# BQ40Z50.net
KiCad netlist of a schematic drawn in Altium Designer
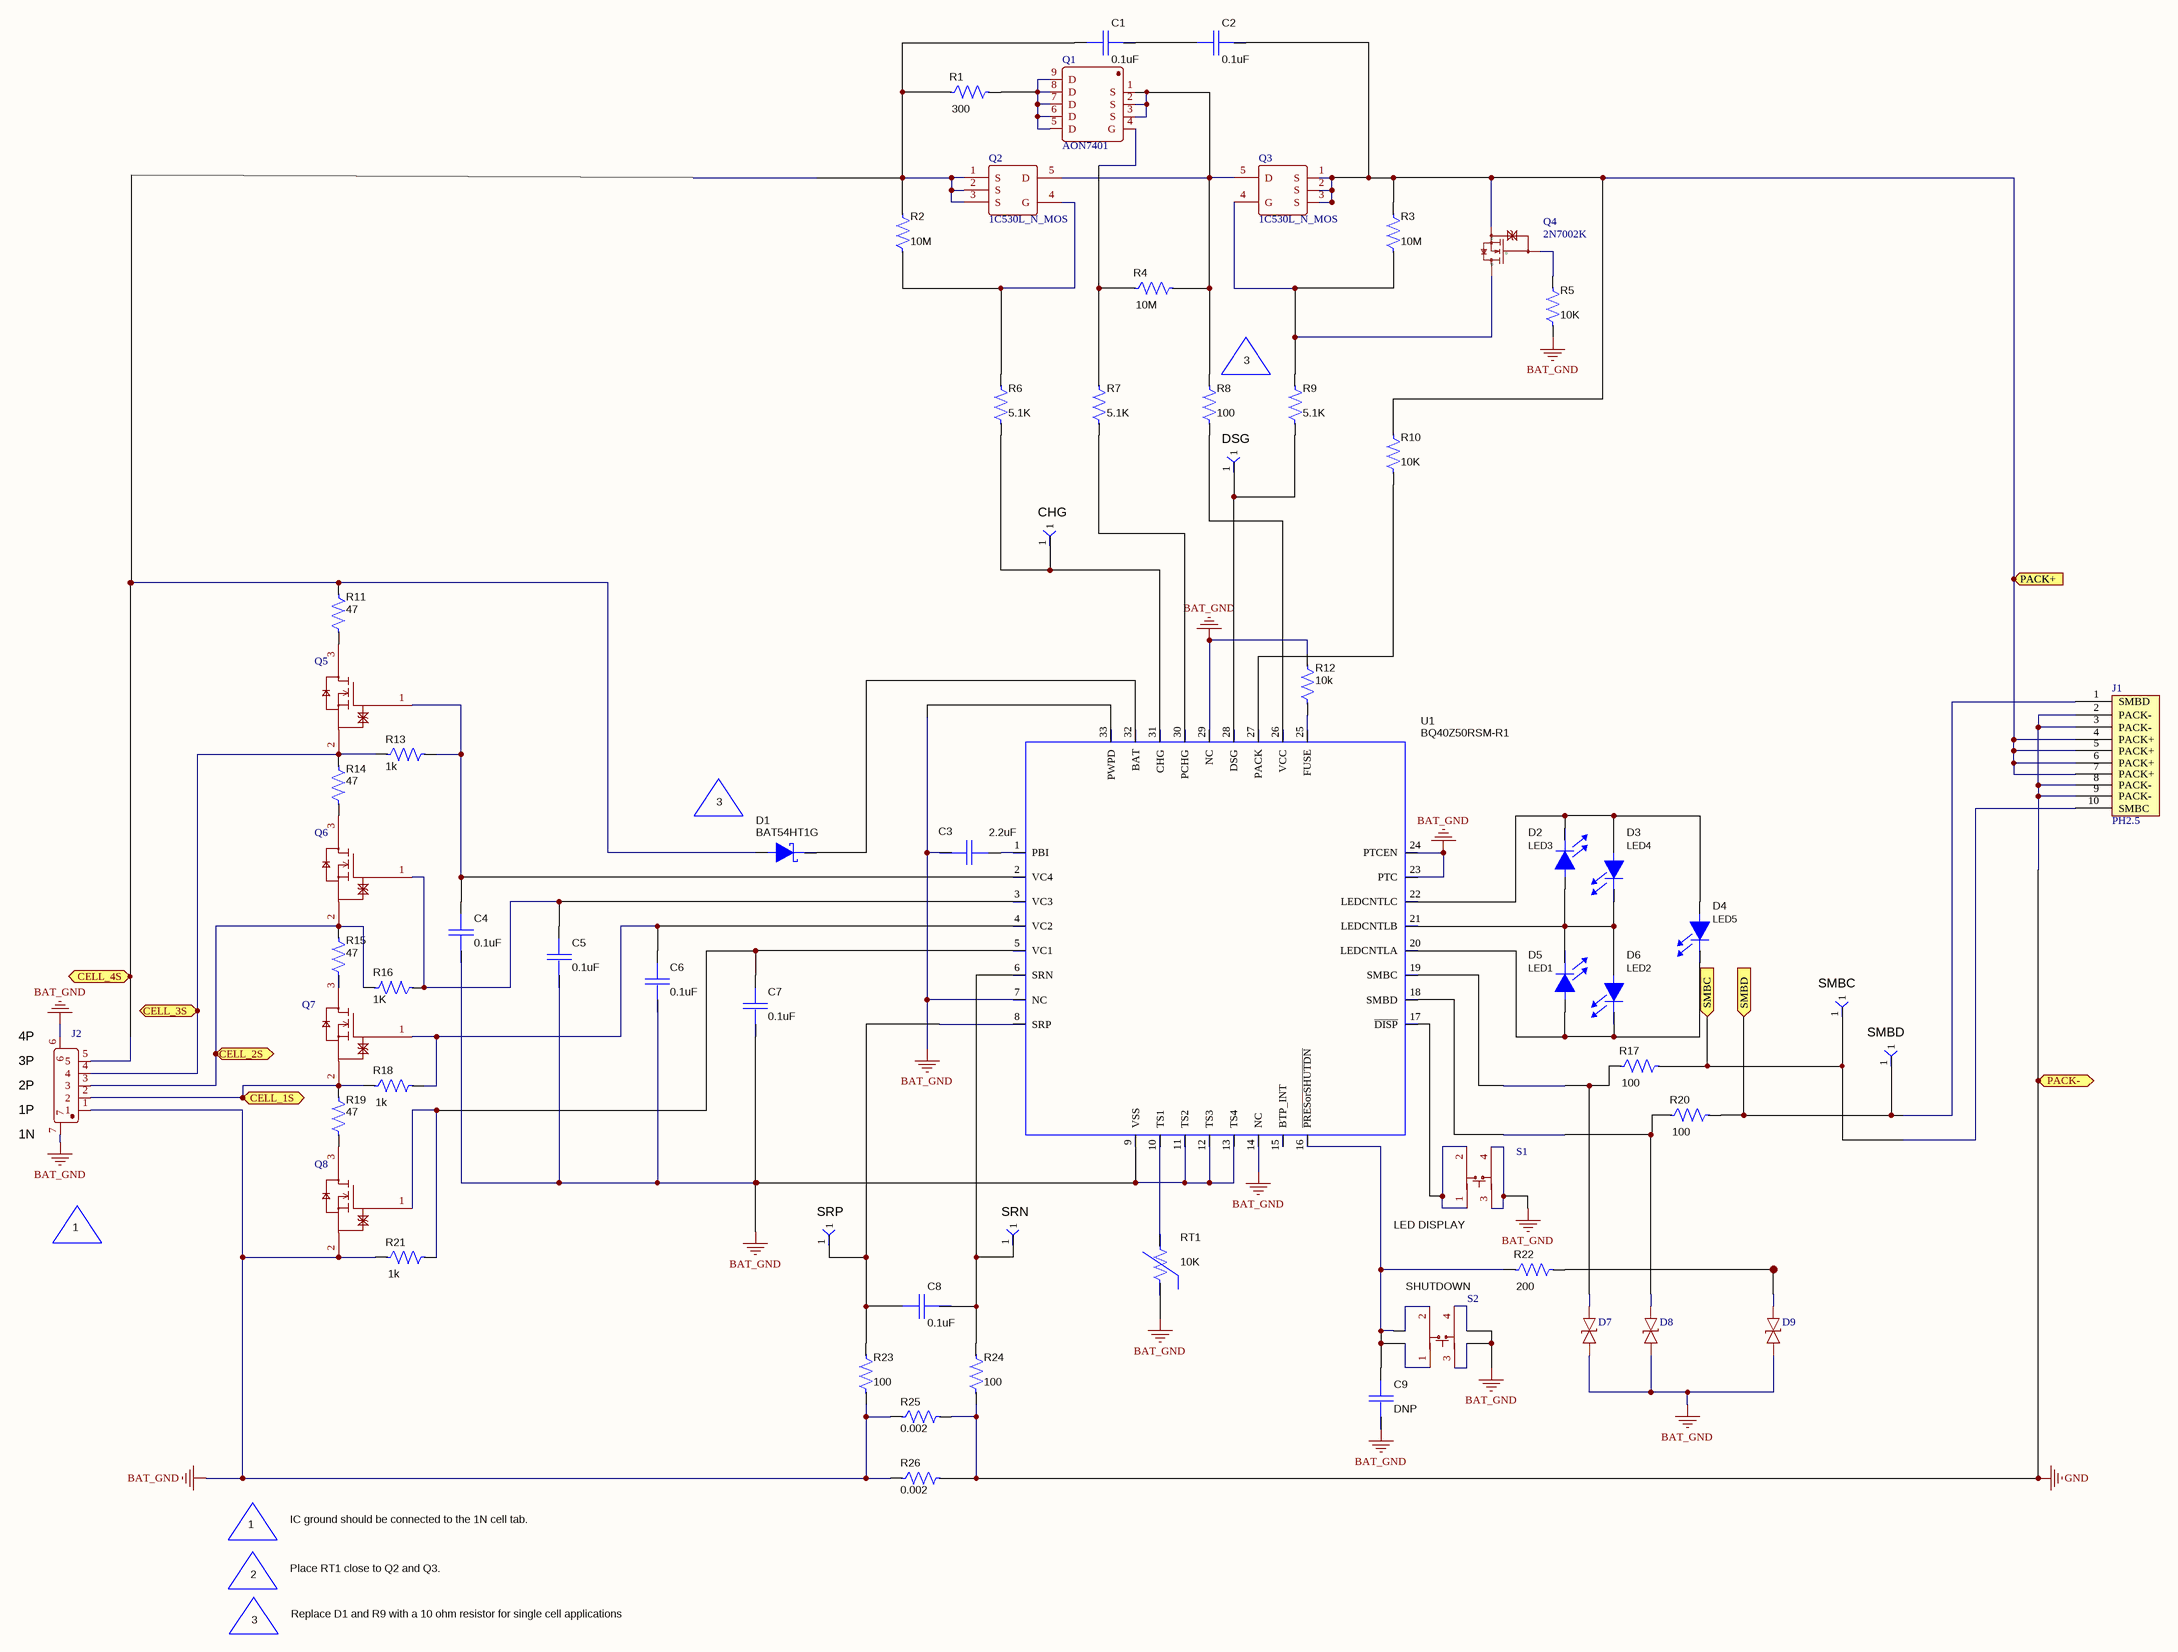
[diagram p0: BQ40Z50.SchDoc]

(export (version "E")
  (design (tool "Eeschema 10.0.6"))
  (components
    (comp (ref "C1")
      (value "0.1uF")
      (footprint "C603")
      (description "Capacitor, Ceramic Chip, 50V, X7R, ±20%")
      (fields (field (name "MANUFACTURER") "Kemet") (field (name "PARTNUMBER") "C0603C104M5RACTU"))
      (libsource (lib "PADSlegacy_Passive") (part "C0603"))
    )
    (comp (ref "C2")
      (value "0.1uF")
      (footprint "C603")
      (description "Capacitor, Ceramic Chip, 50V, X7R, ±20%")
      (fields (field (name "MANUFACTURER") "Kemet") (field (name "PARTNUMBER") "C0603C104M5RACTU"))
      (libsource (lib "PADSlegacy_Passive") (part "C0603"))
    )
    (comp (ref "C3")
      (value "2.2uF")
      (footprint "C0805")
      (description "Capacitor, Ceramic Chip, 25V, X7R ±20%")
      (fields (field (name "MANUFACTURER") "TDK") (field (name "PARTNUMBER") "C2012X7R1E225M085AB"))
      (libsource (lib "PADSlegacy_Passive") (part "C0805"))
    )
    (comp (ref "C4")
      (value "0.1uF")
      (footprint "C603")
      (description "Capacitor, Ceramic Chip, 50V, X7R, ±20%")
      (fields (field (name "MANUFACTURER") "Kemet") (field (name "PARTNUMBER") "C0603C104M5RACTU"))
      (libsource (lib "PADSlegacy_Passive") (part "C0603"))
    )
    (comp (ref "C5")
      (value "0.1uF")
      (footprint "C603")
      (description "Capacitor, Ceramic Chip, 50V, X7R, ±20%")
      (fields (field (name "MANUFACTURER") "Kemet") (field (name "PARTNUMBER") "C0603C104M5RACTU"))
      (libsource (lib "PADSlegacy_Passive") (part "C0603"))
    )
    (comp (ref "C6")
      (value "0.1uF")
      (footprint "C603")
      (description "Capacitor, Ceramic Chip, 50V, X7R, ±20%")
      (fields (field (name "MANUFACTURER") "Kemet") (field (name "PARTNUMBER") "C0603C104M5RACTU"))
      (libsource (lib "PADSlegacy_Passive") (part "C0603"))
    )
    (comp (ref "C7")
      (value "0.1uF")
      (footprint "C603")
      (description "Capacitor, Ceramic Chip, 50V, X7R, ±20%")
      (fields (field (name "MANUFACTURER") "Kemet") (field (name "PARTNUMBER") "C0603C104M5RACTU"))
      (libsource (lib "PADSlegacy_Passive") (part "C0603"))
    )
    (comp (ref "C8")
      (value "0.1uF")
      (footprint "C603")
      (description "Capacitor, Ceramic Chip, 50V, X7R, ±20%")
      (fields (field (name "MANUFACTURER") "Kemet") (field (name "PARTNUMBER") "C0603C104M5RACTU"))
      (libsource (lib "PADSlegacy_Passive") (part "C0603"))
    )
    (comp (ref "C9")
      (value "DNP")
      (footprint "C603")
      (description "Capacitor, Ceramic Chip, 50V, X7R, ±20%")
      (fields (field (name "MANUFACTURER") "Kemet") (field (name "PARTNUMBER") "C0603C104M5RACTU"))
      (libsource (lib "PADSlegacy_Passive") (part "C0603"))
    )
    (comp (ref "D1")
      (value "BAT54HT1G")
      (footprint "SOD-323")
      (description "Diode, Schottky, 200-mA, 30-V")
      (fields (field (name "MANUFACTURER") "On Semi") (field (name "Comment") "D-BAT54HT1"))
      (libsource (lib "PADSlegacy_Active") (part "D-BAT54HT1"))
    )
    (comp (ref "D2")
      (value "D_LED_SML-LXR1206USBC-TR")
      (footprint "LED0805")
      (description "Diode, LED, 2X3mm 565nm GRN WTR CLR SMD")
      (fields (field (name "PARTNUMBER") "SML-LX23GC") (field (name "MANUFACTURER") "Lumex"))
      (libsource (lib "PADSlegacy_Active") (part "D_LED_SML-LXR1206USBC-TR"))
    )
    (comp (ref "D3")
      (value "D_LED_SML-LXR1206USBC-TR")
      (footprint "LED0805")
      (description "Diode, LED, 2X3mm 565nm GRN WTR CLR SMD")
      (fields (field (name "PARTNUMBER") "SML-LX23GC") (field (name "MANUFACTURER") "Lumex"))
      (libsource (lib "PADSlegacy_Active") (part "D_LED_SML-LXR1206USBC-TR"))
    )
    (comp (ref "D4")
      (value "D_LED_SML-LXR1206USBC-TR")
      (footprint "LED0805")
      (description "Diode, LED, 2X3mm 565nm GRN WTR CLR SMD")
      (fields (field (name "PARTNUMBER") "SML-LX23GC") (field (name "MANUFACTURER") "Lumex"))
      (libsource (lib "PADSlegacy_Active") (part "D_LED_SML-LXR1206USBC-TR"))
    )
    (comp (ref "D5")
      (value "D_LED_SML-LXR1206USBC-TR")
      (footprint "LED0805")
      (description "Diode, LED, 2X3mm 565nm GRN WTR CLR SMD")
      (fields (field (name "PARTNUMBER") "SML-LX23GC") (field (name "MANUFACTURER") "Lumex"))
      (libsource (lib "PADSlegacy_Active") (part "D_LED_SML-LXR1206USBC-TR"))
    )
    (comp (ref "D6")
      (value "D_LED_SML-LXR1206USBC-TR")
      (footprint "LED0805")
      (description "Diode, LED, 2X3mm 565nm GRN WTR CLR SMD")
      (fields (field (name "PARTNUMBER") "SML-LX23GC") (field (name "MANUFACTURER") "Lumex"))
      (libsource (lib "PADSlegacy_Active") (part "D_LED_SML-LXR1206USBC-TR"))
    )
    (comp (ref "D7")
      (value "ESD_Diode")
      (footprint "ESD_Diode")
      (libsource (lib "BQ4050") (part "ESD_Diode"))
    )
    (comp (ref "D8")
      (value "ESD_Diode")
      (footprint "ESD_Diode")
      (libsource (lib "BQ4050") (part "ESD_Diode"))
    )
    (comp (ref "D9")
      (value "ESD_Diode")
      (footprint "ESD_Diode")
      (libsource (lib "BQ4050") (part "ESD_Diode"))
    )
    (comp (ref "J1") (value "PH2.5") (footprint "PH2.5") (libsource (lib "BQ4050") (part "PH2.5")))
    (comp (ref "J2") (value "SMD_1.25") (footprint "SMD_1.25") (libsource (lib "BQ4050") (part "SMD_1.25")))
    (comp (ref "Q1") (value "AON7401") (footprint "DFN-8") (libsource (lib "BQ4050") (part "AON7401")))
    (comp (ref "Q2")
      (value "1C530L_N_MOS")
      (footprint "LFPAK")
      (libsource (lib "BQ4050") (part "1C530L_N_MOS"))
    )
    (comp (ref "Q3")
      (value "1C530L_N_MOS")
      (footprint "LFPAK")
      (libsource (lib "BQ4050") (part "1C530L_N_MOS"))
    )
    (comp (ref "Q4") (value "2N7002K") (footprint "2N7002K") (libsource (lib "BQ4050") (part "2N7002K")))
    (comp (ref "Q5")
      (value "DMN601K")
      (footprint "SOT-23 - duplicate")
      (libsource (lib "BQ4050") (part "DMN601K"))
    )
    (comp (ref "Q6")
      (value "DMN601K")
      (footprint "SOT-23 - duplicate")
      (libsource (lib "BQ4050") (part "DMN601K"))
    )
    (comp (ref "Q7")
      (value "DMN601K")
      (footprint "SOT-23 - duplicate")
      (libsource (lib "BQ4050") (part "DMN601K"))
    )
    (comp (ref "Q8")
      (value "DMN601K")
      (footprint "SOT-23 - duplicate")
      (libsource (lib "BQ4050") (part "DMN601K"))
    )
    (comp (ref "R1")
      (value "300")
      (footprint "R2512")
      (description "Resistor, Chip 1W, 5%")
      (fields (field (name "PARTNUMBER") "CRCW2512300RJNEG") (field (name "MANUFACTURER") "Vishay-Dale"))
      (libsource (lib "PADSlegacy_Passive") (part "R2512_5%"))
    )
    (comp (ref "R2")
      (value "10M")
      (footprint "0603")
      (description "Resistor, Chip, 1/10W, 5%")
      (fields (field (name "PARTNUMBER") "CRCW060310M0JNEA") (field (name "MANUFACTURER") "Vishay-Dale"))
      (libsource (lib "PADSlegacy_Passive") (part "R0603_1%"))
    )
    (comp (ref "R3")
      (value "10M")
      (footprint "0603")
      (description "Resistor, Chip, 1/10W, 5%")
      (fields (field (name "PARTNUMBER") "CRCW060310M0JNEA") (field (name "MANUFACTURER") "Vishay-Dale"))
      (libsource (lib "PADSlegacy_Passive") (part "R0603_1%"))
    )
    (comp (ref "R4")
      (value "10M")
      (footprint "0603")
      (description "Resistor, Chip, 1/10W, 5%")
      (fields (field (name "PARTNUMBER") "CRCW060310M0JNEA") (field (name "MANUFACTURER") "Vishay-Dale"))
      (libsource (lib "PADSlegacy_Passive") (part "R0603_1%"))
    )
    (comp (ref "R5")
      (value "10K")
      (footprint "0603")
      (description "Resistor, Chip, 1/10W, 5%")
      (fields (field (name "PARTNUMBER") "CRCW060310M0JNEA") (field (name "MANUFACTURER") "Vishay-Dale"))
      (libsource (lib "PADSlegacy_Passive") (part "R0603_1%"))
    )
    (comp (ref "R6")
      (value "5.1K")
      (footprint "0603")
      (description "Resistor, Chip, 1/10W, 5%")
      (fields (field (name "PARTNUMBER") "CRCW06035K10JNEA") (field (name "MANUFACTURER") "Vishay-Dale"))
      (libsource (lib "PADSlegacy_Passive") (part "R0603_1%"))
    )
    (comp (ref "R7")
      (value "5.1K")
      (footprint "0603")
      (description "Resistor, Chip, 1/10W, 5%")
      (fields (field (name "PARTNUMBER") "CRCW06035K10JNEA") (field (name "MANUFACTURER") "Vishay-Dale"))
      (libsource (lib "PADSlegacy_Passive") (part "R0603_1%"))
    )
    (comp (ref "R8")
      (value "100")
      (footprint "0603")
      (description "Resistor, Chip, 1/10W, 5%")
      (fields (field (name "PARTNUMBER") "CRCW0603100RJNEAHP") (field (name "MANUFACTURER") "Vishay-Dale"))
      (libsource (lib "PADSlegacy_Passive") (part "R0603_1%"))
    )
    (comp (ref "R9")
      (value "5.1K")
      (footprint "0603")
      (description "Resistor, Chip, 1/10W, 5%")
      (fields (field (name "PARTNUMBER") "CRCW06035K10JNEA") (field (name "MANUFACTURER") "Vishay-Dale"))
      (libsource (lib "PADSlegacy_Passive") (part "R0603_1%"))
    )
    (comp (ref "R10")
      (value "10K")
      (footprint "0603")
      (description "Resistor, Chip, 1/10W, 5%")
      (fields (field (name "PARTNUMBER") "CRCW060310K0JNEA") (field (name "MANUFACTURER") "Vishay-Dale"))
      (libsource (lib "PADSlegacy_Passive") (part "R0603_1%"))
    )
    (comp (ref "R11")
      (value "47")
      (footprint "R1206")
      (description "Resistor, Chip 1 watt, ±1%, 50 ppm")
      (fields (field (name "PARTNUMBER") "CSR1206-0R001F1") (field (name "MANUFACTURER") "Reidon"))
      (libsource (lib "BQ4050") (part "R1206_1%"))
    )
    (comp (ref "R12")
      (value "10k")
      (footprint "0603")
      (description "Resistor, Chip, 1/10W, 5%")
      (fields (field (name "PARTNUMBER") "CRCW06035K10JNEA") (field (name "MANUFACTURER") "Vishay-Dale"))
      (libsource (lib "PADSlegacy_Passive") (part "R0603_1%"))
    )
    (comp (ref "R13")
      (value "1k")
      (footprint "0603")
      (description "Resistor, Chip, 1/10W, 5%")
      (fields (field (name "PARTNUMBER") "CRCW0603100RJNEAHP") (field (name "MANUFACTURER") "Vishay-Dale"))
      (libsource (lib "PADSlegacy_Passive") (part "R0603_1%"))
    )
    (comp (ref "R14")
      (value "47")
      (footprint "R1206")
      (description "Resistor, Chip 1 watt, ±1%, 50 ppm")
      (fields (field (name "PARTNUMBER") "CSR1206-0R001F1") (field (name "MANUFACTURER") "Reidon"))
      (libsource (lib "BQ4050") (part "R1206_1%"))
    )
    (comp (ref "R15")
      (value "47")
      (footprint "R1206")
      (description "Resistor, Chip 1 watt, ±1%, 50 ppm")
      (fields (field (name "PARTNUMBER") "CSR1206-0R001F1") (field (name "MANUFACTURER") "Reidon"))
      (libsource (lib "BQ4050") (part "R1206_1%"))
    )
    (comp (ref "R16")
      (value "1K")
      (footprint "0603")
      (description "Resistor, Chip, 1/10W, 5%")
      (fields (field (name "PARTNUMBER") "CRCW0603100RJNEAHP") (field (name "MANUFACTURER") "Vishay-Dale"))
      (libsource (lib "PADSlegacy_Passive") (part "R0603_1%"))
    )
    (comp (ref "R17")
      (value "100")
      (footprint "0603")
      (description "Resistor, Chip, 1/10W, 5%")
      (fields (field (name "PARTNUMBER") "CRCW0603100RJNEAHP") (field (name "MANUFACTURER") "Vishay-Dale"))
      (libsource (lib "PADSlegacy_Passive") (part "R0603_1%"))
    )
    (comp (ref "R18")
      (value "1k")
      (footprint "0603")
      (description "Resistor, Chip, 1/10W, 5%")
      (fields (field (name "PARTNUMBER") "CRCW0603100RJNEAHP") (field (name "MANUFACTURER") "Vishay-Dale"))
      (libsource (lib "PADSlegacy_Passive") (part "R0603_1%"))
    )
    (comp (ref "R19")
      (value "47")
      (footprint "R1206")
      (description "Resistor, Chip 1 watt, ±1%, 50 ppm")
      (fields (field (name "PARTNUMBER") "CSR1206-0R001F1") (field (name "MANUFACTURER") "Reidon"))
      (libsource (lib "BQ4050") (part "R1206_1%"))
    )
    (comp (ref "R20")
      (value "100")
      (footprint "0603")
      (description "Resistor, Chip, 1/10W, 5%")
      (fields (field (name "PARTNUMBER") "CRCW0603100RJNEAHP") (field (name "MANUFACTURER") "Vishay-Dale"))
      (libsource (lib "PADSlegacy_Passive") (part "R0603_1%"))
    )
    (comp (ref "R21")
      (value "1k")
      (footprint "0603")
      (description "Resistor, Chip, 1/10W, 5%")
      (fields (field (name "PARTNUMBER") "CRCW0603100RJNEAHP") (field (name "MANUFACTURER") "Vishay-Dale"))
      (libsource (lib "PADSlegacy_Passive") (part "R0603_1%"))
    )
    (comp (ref "R22")
      (value "200")
      (footprint "0603")
      (description "Resistor, Chip, 1/16W, 5%")
      (fields (field (name "PARTNUMBER") "CRCW0603200RJNEA") (field (name "MANUFACTURER") "Vishay-Dale"))
      (libsource (lib "PADSlegacy_Passive") (part "R0603_1%"))
    )
    (comp (ref "R23")
      (value "100")
      (footprint "0603")
      (description "Resistor, Chip, 1/10W, 5%")
      (fields (field (name "PARTNUMBER") "CRCW0603100RJNEAHP") (field (name "MANUFACTURER") "Vishay-Dale"))
      (libsource (lib "PADSlegacy_Passive") (part "R0603_1%"))
    )
    (comp (ref "R24")
      (value "100")
      (footprint "0603")
      (description "Resistor, Chip, 1/10W, 5%")
      (fields (field (name "PARTNUMBER") "CRCW0603100RJNEAHP") (field (name "MANUFACTURER") "Vishay-Dale"))
      (libsource (lib "PADSlegacy_Passive") (part "R0603_1%"))
    )
    (comp (ref "R25")
      (value "0.002")
      (footprint "R2512")
      (description "Resistor, Chip 1W, 5%")
      (fields (field (name "PARTNUMBER") "CRCW2512300RJNEG") (field (name "MANUFACTURER") "Vishay-Dale"))
      (libsource (lib "BQ4050") (part "R2512_5%"))
    )
    (comp (ref "R26")
      (value "0.002")
      (footprint "R2512")
      (description "Resistor, Chip 1W, 5%")
      (fields (field (name "PARTNUMBER") "CRCW2512300RJNEG") (field (name "MANUFACTURER") "Vishay-Dale"))
      (libsource (lib "BQ4050") (part "R2512_5%"))
    )
    (comp (ref "RT1")
      (value "10K")
      (footprint "C0805")
      (description "Thermistor, NTC, 3-A")
      (fields (field (name "MANUFACTURER") "Semitec") (field (name "PARTNUMBER") "103AT-2"))
      (libsource (lib "PADSlegacy_Passive") (part "THERMISTOR-103AT"))
    )
    (comp (ref "S1") (value "SW_SMD") (footprint "SW_SMD") (libsource (lib "BQ4050") (part "SW_SMD")))
    (comp (ref "S2") (value "SW_SMD") (footprint "SW_SMD") (libsource (lib "BQ4050") (part "SW_SMD")))
    (comp (ref "TP1")
      (value "TP_.040_SMT")
      (footprint "TP_.040_SMT")
      (description "Test point, 40 mil SMT")
      (fields (field (name "MANUFACTURER") "None"))
      (libsource (lib "PADSlegacy_Hardware") (part "TP_.040_SMT"))
    )
    (comp (ref "TP2")
      (value "TP_.040_SMT")
      (footprint "TP_.040_SMT")
      (description "Test point, 40 mil SMT")
      (fields (field (name "MANUFACTURER") "None"))
      (libsource (lib "PADSlegacy_Hardware") (part "TP_.040_SMT"))
    )
    (comp (ref "TP3")
      (value "TP_.040_SMT")
      (footprint "TP_.040_SMT")
      (description "Test point, 40 mil SMT")
      (fields (field (name "MANUFACTURER") "None"))
      (libsource (lib "PADSlegacy_Hardware") (part "TP_.040_SMT"))
    )
    (comp (ref "TP4")
      (value "TP_.040_SMT")
      (footprint "TP_.040_SMT")
      (description "Test point, 40 mil SMT")
      (fields (field (name "MANUFACTURER") "None"))
      (libsource (lib "PADSlegacy_Hardware") (part "TP_.040_SMT"))
    )
    (comp (ref "TP5")
      (value "TP_40_SMT")
      (footprint "TP_40_SMT")
      (description "Test point, 40 mil SMT")
      (fields (field (name "MANUFACTURER") "None"))
      (libsource (lib "PADSlegacy_Hardware") (part "TP_40_SMT"))
    )
    (comp (ref "TP6")
      (value "TP_.040_SMT")
      (footprint "TP_.040_SMT")
      (description "Test point, 40 mil SMT")
      (fields (field (name "MANUFACTURER") "None"))
      (libsource (lib "PADSlegacy_Hardware") (part "TP_.040_SMT"))
    )
    (comp (ref "U1")
      (value "BQ40Z50RSM-R1")
      (footprint "QFP-32P_(RSM)")
      (description "IC, 2 to 4-Series Li-Ion Battery Pack Manager")
      (fields (field (name "MANUFACTURER") "TI") (field (name "Comment") "BQ40Z55RSM"))
      (libsource (lib "BQ4050") (part "BQ40Z55RSM"))
    )
  )
  (nets
    (net (code "1") (name "/CELL_1S") (class "Default")
      (node (ref "J2") (pin "2") (pinfunction "2_2") (pintype "passive"))
      (node (ref "Q7") (pin "2") (pinfunction "S_2") (pintype "passive"))
      (node (ref "R18") (pin "1") (pinfunction "1_1") (pintype "passive"))
      (node (ref "R19") (pin "2") (pinfunction "2_2") (pintype "passive"))
    )
    (net (code "2") (name "/CELL_2S") (class "Default")
      (node (ref "J2") (pin "3") (pinfunction "3_3") (pintype "passive"))
      (node (ref "Q6") (pin "2") (pinfunction "S_2") (pintype "passive"))
      (node (ref "R15") (pin "2") (pinfunction "2_2") (pintype "passive"))
      (node (ref "R16") (pin "2") (pinfunction "2_2") (pintype "passive"))
    )
    (net (code "3") (name "/CELL_3S") (class "Default")
      (node (ref "J2") (pin "4") (pinfunction "4_4") (pintype "passive"))
      (node (ref "Q5") (pin "2") (pinfunction "S_2") (pintype "passive"))
      (node (ref "R13") (pin "1") (pinfunction "1_1") (pintype "passive"))
      (node (ref "R14") (pin "1") (pinfunction "1_1") (pintype "passive"))
    )
    (net (code "4") (name "/CELL_4S") (class "Default")
      (node (ref "C1") (pin "2") (pinfunction "2_2") (pintype "passive"))
      (node (ref "D1") (pin "2") (pinfunction "A_2") (pintype "passive"))
      (node (ref "J2") (pin "5") (pinfunction "5_5") (pintype "passive"))
      (node (ref "Q2") (pin "1") (pinfunction "S_1") (pintype "passive"))
      (node (ref "Q2") (pin "2") (pinfunction "S_2") (pintype "passive"))
      (node (ref "Q2") (pin "3") (pinfunction "S_3") (pintype "passive"))
      (node (ref "R1") (pin "1") (pinfunction "1_1") (pintype "passive"))
      (node (ref "R11") (pin "1") (pinfunction "1_1") (pintype "passive"))
      (node (ref "R2") (pin "2") (pinfunction "2_2") (pintype "passive"))
    )
    (net (code "5") (name "/PACK+") (class "Default")
      (node (ref "C2") (pin "1") (pinfunction "1_1") (pintype "passive"))
      (node (ref "J1") (pin "4") (pinfunction "PACK+_4") (pintype "passive"))
      (node (ref "J1") (pin "5") (pinfunction "PACK+_5") (pintype "passive"))
      (node (ref "J1") (pin "6") (pinfunction "PACK+_6") (pintype "passive"))
      (node (ref "J1") (pin "7") (pinfunction "PACK+_7") (pintype "passive"))
      (node (ref "Q3") (pin "1") (pinfunction "S_1") (pintype "passive"))
      (node (ref "Q3") (pin "2") (pinfunction "S_2") (pintype "passive"))
      (node (ref "Q3") (pin "3") (pinfunction "S_3") (pintype "passive"))
      (node (ref "Q4") (pin "2") (pinfunction "S_2") (pintype "passive"))
      (node (ref "R10") (pin "2") (pinfunction "2_2") (pintype "passive"))
      (node (ref "R3") (pin "2") (pinfunction "2_2") (pintype "passive"))
    )
    (net (code "6") (name "/SMBC") (class "Default")
      (node (ref "J1") (pin "10") (pinfunction "SMBC_10") (pintype "passive"))
      (node (ref "R17") (pin "2") (pinfunction "2_2") (pintype "passive"))
      (node (ref "TP3") (pin "1") (pinfunction "1_1") (pintype "passive"))
    )
    (net (code "7") (name "/SMBD") (class "Default")
      (node (ref "J1") (pin "1") (pinfunction "SMBD_1") (pintype "passive"))
      (node (ref "R20") (pin "2") (pinfunction "2_2") (pintype "passive"))
      (node (ref "TP4") (pin "1") (pinfunction "1_1") (pintype "passive"))
    )
    (net (code "8") (name "BAT_GND") (class "Default")
      (node (ref "C3") (pin "1") (pinfunction "1_1") (pintype "passive"))
      (node (ref "C4") (pin "1") (pinfunction "1_1") (pintype "passive"))
      (node (ref "C5") (pin "1") (pinfunction "1_1") (pintype "passive"))
      (node (ref "C6") (pin "1") (pinfunction "1_1") (pintype "passive"))
      (node (ref "C7") (pin "1") (pinfunction "1_1") (pintype "passive"))
      (node (ref "C9") (pin "1") (pinfunction "1_1") (pintype "passive"))
      (node (ref "D7") (pin "1") (pinfunction "1_1") (pintype "passive"))
      (node (ref "D8") (pin "1") (pinfunction "1_1") (pintype "passive"))
      (node (ref "D9") (pin "1") (pinfunction "1_1") (pintype "passive"))
      (node (ref "J2") (pin "1") (pinfunction "1_1") (pintype "passive"))
      (node (ref "J2") (pin "6") (pinfunction "6_6") (pintype "passive"))
      (node (ref "J2") (pin "7") (pinfunction "7_7") (pintype "passive"))
      (node (ref "Q8") (pin "2") (pinfunction "S_2") (pintype "passive"))
      (node (ref "R12") (pin "2") (pinfunction "2_2") (pintype "passive"))
      (node (ref "R21") (pin "1") (pinfunction "1_1") (pintype "passive"))
      (node (ref "R23") (pin "1") (pinfunction "1_1") (pintype "passive"))
      (node (ref "R25") (pin "1") (pinfunction "1_1") (pintype "passive"))
      (node (ref "R26") (pin "1") (pinfunction "1_1") (pintype "passive"))
      (node (ref "R5") (pin "1") (pinfunction "1_1") (pintype "passive"))
      (node (ref "RT1") (pin "1") (pinfunction "1_1") (pintype "passive"))
      (node (ref "S1") (pin "3") (pinfunction "3_3") (pintype "passive"))
      (node (ref "S1") (pin "4") (pinfunction "4_4") (pintype "passive"))
      (node (ref "S2") (pin "3") (pinfunction "3_3") (pintype "passive"))
      (node (ref "S2") (pin "4") (pinfunction "4_4") (pintype "passive"))
      (node (ref "U1") (pin "11") (pinfunction "TS2_11") (pintype "passive"))
      (node (ref "U1") (pin "12") (pinfunction "TS3_12") (pintype "passive"))
      (node (ref "U1") (pin "13") (pinfunction "TS4_13") (pintype "passive"))
      (node (ref "U1") (pin "14") (pinfunction "NC_14") (pintype "passive"))
      (node (ref "U1") (pin "23") (pinfunction "PTC_23") (pintype "passive"))
      (node (ref "U1") (pin "24") (pinfunction "PTCEN_24") (pintype "passive"))
      (node (ref "U1") (pin "29") (pinfunction "NC_29") (pintype "passive"))
      (node (ref "U1") (pin "33") (pinfunction "PWPD_33") (pintype "passive"))
      (node (ref "U1") (pin "7") (pinfunction "NC_7") (pintype "passive"))
      (node (ref "U1") (pin "9") (pinfunction "VSS_9") (pintype "passive"))
    )
    (net (code "9") (name "GND") (class "Default")
      (node (ref "J1") (pin "2") (pinfunction "PACK-_2") (pintype "passive"))
      (node (ref "J1") (pin "3") (pinfunction "PACK-_3") (pintype "passive"))
      (node (ref "J1") (pin "8") (pinfunction "PACK-_8") (pintype "passive"))
      (node (ref "J1") (pin "9") (pinfunction "PACK-_9") (pintype "passive"))
      (node (ref "R24") (pin "1") (pinfunction "1_1") (pintype "passive"))
      (node (ref "R25") (pin "2") (pinfunction "2_2") (pintype "passive"))
      (node (ref "R26") (pin "2") (pinfunction "2_2") (pintype "passive"))
    )
    (net (code "10") (name "Net-(C1-Pad1)") (class "Default")
      (node (ref "C1") (pin "1") (pinfunction "1_1") (pintype "passive"))
      (node (ref "C2") (pin "2") (pinfunction "2_2") (pintype "passive"))
    )
    (net (code "11") (name "Net-(D1-C)") (class "Default")
      (node (ref "D1") (pin "1") (pinfunction "C_1") (pintype "passive"))
      (node (ref "U1") (pin "32") (pinfunction "BAT_32") (pintype "passive"))
    )
    (net (code "12") (name "Net-(D2-A)") (class "Default")
      (node (ref "D2") (pin "2") (pinfunction "A_2") (pintype "passive"))
      (node (ref "D3") (pin "1") (pinfunction "C_1") (pintype "passive"))
      (node (ref "D5") (pin "1") (pinfunction "C_1") (pintype "passive"))
      (node (ref "D6") (pin "2") (pinfunction "A_2") (pintype "passive"))
      (node (ref "U1") (pin "21") (pinfunction "LEDCNTLB_21") (pintype "passive"))
    )
    (net (code "13") (name "Net-(D2-C)") (class "Default")
      (node (ref "D2") (pin "1") (pinfunction "C_1") (pintype "passive"))
      (node (ref "D3") (pin "2") (pinfunction "A_2") (pintype "passive"))
      (node (ref "D4") (pin "2") (pinfunction "A_2") (pintype "passive"))
      (node (ref "U1") (pin "22") (pinfunction "LEDCNTLC_22") (pintype "passive"))
    )
    (net (code "14") (name "Net-(D4-C)") (class "Default")
      (node (ref "D4") (pin "1") (pinfunction "C_1") (pintype "passive"))
      (node (ref "D5") (pin "2") (pinfunction "A_2") (pintype "passive"))
      (node (ref "D6") (pin "1") (pinfunction "C_1") (pintype "passive"))
      (node (ref "U1") (pin "20") (pinfunction "LEDCNTLA_20") (pintype "passive"))
    )
    (net (code "15") (name "Net-(D9-Pad2)") (class "Default")
      (node (ref "D9") (pin "2") (pinfunction "2_2") (pintype "passive"))
      (node (ref "R22") (pin "2") (pinfunction "2_2") (pintype "passive"))
    )
    (net (code "16") (name "Net-(Q1-D-Pad5)") (class "Default")
      (node (ref "Q1") (pin "5") (pinfunction "D_5") (pintype "passive"))
      (node (ref "Q1") (pin "6") (pinfunction "D_6") (pintype "passive"))
      (node (ref "Q1") (pin "7") (pinfunction "D_7") (pintype "passive"))
      (node (ref "Q1") (pin "8") (pinfunction "D_8") (pintype "passive"))
      (node (ref "Q1") (pin "9") (pinfunction "D_9") (pintype "passive"))
      (node (ref "R1") (pin "2") (pinfunction "2_2") (pintype "passive"))
    )
    (net (code "17") (name "Net-(Q1-G)") (class "Default")
      (node (ref "Q1") (pin "4") (pinfunction "G_4") (pintype "passive"))
      (node (ref "R4") (pin "1") (pinfunction "1_1") (pintype "passive"))
      (node (ref "R7") (pin "2") (pinfunction "2_2") (pintype "passive"))
    )
    (net (code "18") (name "Net-(Q2-D)") (class "Default")
      (node (ref "Q1") (pin "1") (pinfunction "S_1") (pintype "passive"))
      (node (ref "Q1") (pin "2") (pinfunction "S_2") (pintype "passive"))
      (node (ref "Q1") (pin "3") (pinfunction "S_3") (pintype "passive"))
      (node (ref "Q2") (pin "5") (pinfunction "D_5") (pintype "passive"))
      (node (ref "Q3") (pin "5") (pinfunction "D_5") (pintype "passive"))
      (node (ref "R4") (pin "2") (pinfunction "2_2") (pintype "passive"))
      (node (ref "R8") (pin "2") (pinfunction "2_2") (pintype "passive"))
    )
    (net (code "19") (name "Net-(Q2-G)") (class "Default")
      (node (ref "Q2") (pin "4") (pinfunction "G_4") (pintype "passive"))
      (node (ref "R2") (pin "1") (pinfunction "1_1") (pintype "passive"))
      (node (ref "R6") (pin "2") (pinfunction "2_2") (pintype "passive"))
    )
    (net (code "20") (name "Net-(Q3-G)") (class "Default")
      (node (ref "Q3") (pin "4") (pinfunction "G_4") (pintype "passive"))
      (node (ref "Q4") (pin "3") (pinfunction "D_3") (pintype "passive"))
      (node (ref "R3") (pin "1") (pinfunction "1_1") (pintype "passive"))
      (node (ref "R9") (pin "2") (pinfunction "2_2") (pintype "passive"))
    )
    (net (code "21") (name "Net-(Q4-G)") (class "Default")
      (node (ref "Q4") (pin "1") (pinfunction "G_1") (pintype "passive"))
      (node (ref "R5") (pin "2") (pinfunction "2_2") (pintype "passive"))
    )
    (net (code "22") (name "Net-(Q5-D)") (class "Default")
      (node (ref "Q5") (pin "3") (pinfunction "D_3") (pintype "passive"))
      (node (ref "R11") (pin "2") (pinfunction "2_2") (pintype "passive"))
    )
    (net (code "23") (name "Net-(Q5-G)") (class "Default")
      (node (ref "C4") (pin "2") (pinfunction "2_2") (pintype "passive"))
      (node (ref "Q5") (pin "1") (pinfunction "G_1") (pintype "passive"))
      (node (ref "R13") (pin "2") (pinfunction "2_2") (pintype "passive"))
      (node (ref "U1") (pin "2") (pinfunction "VC4_2") (pintype "passive"))
    )
    (net (code "24") (name "Net-(Q6-D)") (class "Default")
      (node (ref "Q6") (pin "3") (pinfunction "D_3") (pintype "passive"))
      (node (ref "R14") (pin "2") (pinfunction "2_2") (pintype "passive"))
    )
    (net (code "25") (name "Net-(Q6-G)") (class "Default")
      (node (ref "C5") (pin "2") (pinfunction "2_2") (pintype "passive"))
      (node (ref "Q6") (pin "1") (pinfunction "G_1") (pintype "passive"))
      (node (ref "R16") (pin "1") (pinfunction "1_1") (pintype "passive"))
      (node (ref "U1") (pin "3") (pinfunction "VC3_3") (pintype "passive"))
    )
    (net (code "26") (name "Net-(Q7-D)") (class "Default")
      (node (ref "Q7") (pin "3") (pinfunction "D_3") (pintype "passive"))
      (node (ref "R15") (pin "1") (pinfunction "1_1") (pintype "passive"))
    )
    (net (code "27") (name "Net-(Q7-G)") (class "Default")
      (node (ref "C6") (pin "2") (pinfunction "2_2") (pintype "passive"))
      (node (ref "Q7") (pin "1") (pinfunction "G_1") (pintype "passive"))
      (node (ref "R18") (pin "2") (pinfunction "2_2") (pintype "passive"))
      (node (ref "U1") (pin "4") (pinfunction "VC2_4") (pintype "passive"))
    )
    (net (code "28") (name "Net-(Q8-D)") (class "Default")
      (node (ref "Q8") (pin "3") (pinfunction "D_3") (pintype "passive"))
      (node (ref "R19") (pin "1") (pinfunction "1_1") (pintype "passive"))
    )
    (net (code "29") (name "Net-(Q8-G)") (class "Default")
      (node (ref "C7") (pin "2") (pinfunction "2_2") (pintype "passive"))
      (node (ref "Q8") (pin "1") (pinfunction "G_1") (pintype "passive"))
      (node (ref "R21") (pin "2") (pinfunction "2_2") (pintype "passive"))
      (node (ref "U1") (pin "5") (pinfunction "VC1_5") (pintype "passive"))
    )
    (net (code "30") (name "Net-(U1-CHG)") (class "Default")
      (node (ref "R6") (pin "1") (pinfunction "1_1") (pintype "passive"))
      (node (ref "TP2") (pin "1") (pinfunction "1_1") (pintype "passive"))
      (node (ref "U1") (pin "31") (pinfunction "CHG_31") (pintype "passive"))
    )
    (net (code "31") (name "Net-(U1-DISP)") (class "Default")
      (node (ref "S1") (pin "1") (pinfunction "1_1") (pintype "passive"))
      (node (ref "S1") (pin "2") (pinfunction "2_2") (pintype "passive"))
      (node (ref "U1") (pin "17") (pinfunction "DISP_17") (pintype "passive"))
    )
    (net (code "32") (name "Net-(U1-DSG)") (class "Default")
      (node (ref "R9") (pin "1") (pinfunction "1_1") (pintype "passive"))
      (node (ref "TP1") (pin "1") (pinfunction "1_1") (pintype "passive"))
      (node (ref "U1") (pin "28") (pinfunction "DSG_28") (pintype "passive"))
    )
    (net (code "33") (name "Net-(U1-FUSE)") (class "Default")
      (node (ref "R12") (pin "1") (pinfunction "1_1") (pintype "passive"))
      (node (ref "U1") (pin "25") (pinfunction "FUSE_25") (pintype "passive"))
    )
    (net (code "34") (name "Net-(U1-PACK)") (class "Default")
      (node (ref "R10") (pin "1") (pinfunction "1_1") (pintype "passive"))
      (node (ref "U1") (pin "27") (pinfunction "PACK_27") (pintype "passive"))
    )
    (net (code "35") (name "Net-(U1-PBI)") (class "Default")
      (node (ref "C3") (pin "2") (pinfunction "2_2") (pintype "passive"))
      (node (ref "U1") (pin "1") (pinfunction "PBI_1") (pintype "passive"))
    )
    (net (code "36") (name "Net-(U1-PCHG)") (class "Default")
      (node (ref "R7") (pin "1") (pinfunction "1_1") (pintype "passive"))
      (node (ref "U1") (pin "30") (pinfunction "PCHG_30") (pintype "passive"))
    )
    (net (code "37") (name "Net-(U1-PRESorSHUTDN)") (class "Default")
      (node (ref "C9") (pin "2") (pinfunction "2_2") (pintype "passive"))
      (node (ref "R22") (pin "1") (pinfunction "1_1") (pintype "passive"))
      (node (ref "S2") (pin "1") (pinfunction "1_1") (pintype "passive"))
      (node (ref "S2") (pin "2") (pinfunction "2_2") (pintype "passive"))
      (node (ref "U1") (pin "16") (pinfunction "PRESorSHUTDN_16") (pintype "passive"))
    )
    (net (code "38") (name "Net-(U1-SMBC)") (class "Default")
      (node (ref "D7") (pin "2") (pinfunction "2_2") (pintype "passive"))
      (node (ref "R17") (pin "1") (pinfunction "1_1") (pintype "passive"))
      (node (ref "U1") (pin "19") (pinfunction "SMBC_19") (pintype "passive"))
    )
    (net (code "39") (name "Net-(U1-SMBD)") (class "Default")
      (node (ref "D8") (pin "2") (pinfunction "2_2") (pintype "passive"))
      (node (ref "R20") (pin "1") (pinfunction "1_1") (pintype "passive"))
      (node (ref "U1") (pin "18") (pinfunction "SMBD_18") (pintype "passive"))
    )
    (net (code "40") (name "Net-(U1-SRN)") (class "Default")
      (node (ref "C8") (pin "1") (pinfunction "1_1") (pintype "passive"))
      (node (ref "R24") (pin "2") (pinfunction "2_2") (pintype "passive"))
      (node (ref "TP6") (pin "1") (pinfunction "1_1") (pintype "passive"))
      (node (ref "U1") (pin "6") (pinfunction "SRN_6") (pintype "passive"))
    )
    (net (code "41") (name "Net-(U1-SRP)") (class "Default")
      (node (ref "C8") (pin "2") (pinfunction "2_2") (pintype "passive"))
      (node (ref "R23") (pin "2") (pinfunction "2_2") (pintype "passive"))
      (node (ref "TP5") (pin "1") (pinfunction "1_1") (pintype "passive"))
      (node (ref "U1") (pin "8") (pinfunction "SRP_8") (pintype "passive"))
    )
    (net (code "42") (name "Net-(U1-TS1)") (class "Default")
      (node (ref "RT1") (pin "2") (pinfunction "2_2") (pintype "passive"))
      (node (ref "U1") (pin "10") (pinfunction "TS1_10") (pintype "passive"))
    )
    (net (code "43") (name "Net-(U1-VCC)") (class "Default")
      (node (ref "R8") (pin "1") (pinfunction "1_1") (pintype "passive"))
      (node (ref "U1") (pin "26") (pinfunction "VCC_26") (pintype "passive"))
    )
    (net (code "44") (name "unconnected-(U1-BTP_INT-Pad15)") (class "Default")
      (node (ref "U1") (pin "15") (pinfunction "BTP_INT_15") (pintype "passive"))
    )
  )
)
